# I2C_Keypad.net
KiCad netlist of a schematic drawn in Altium Designer
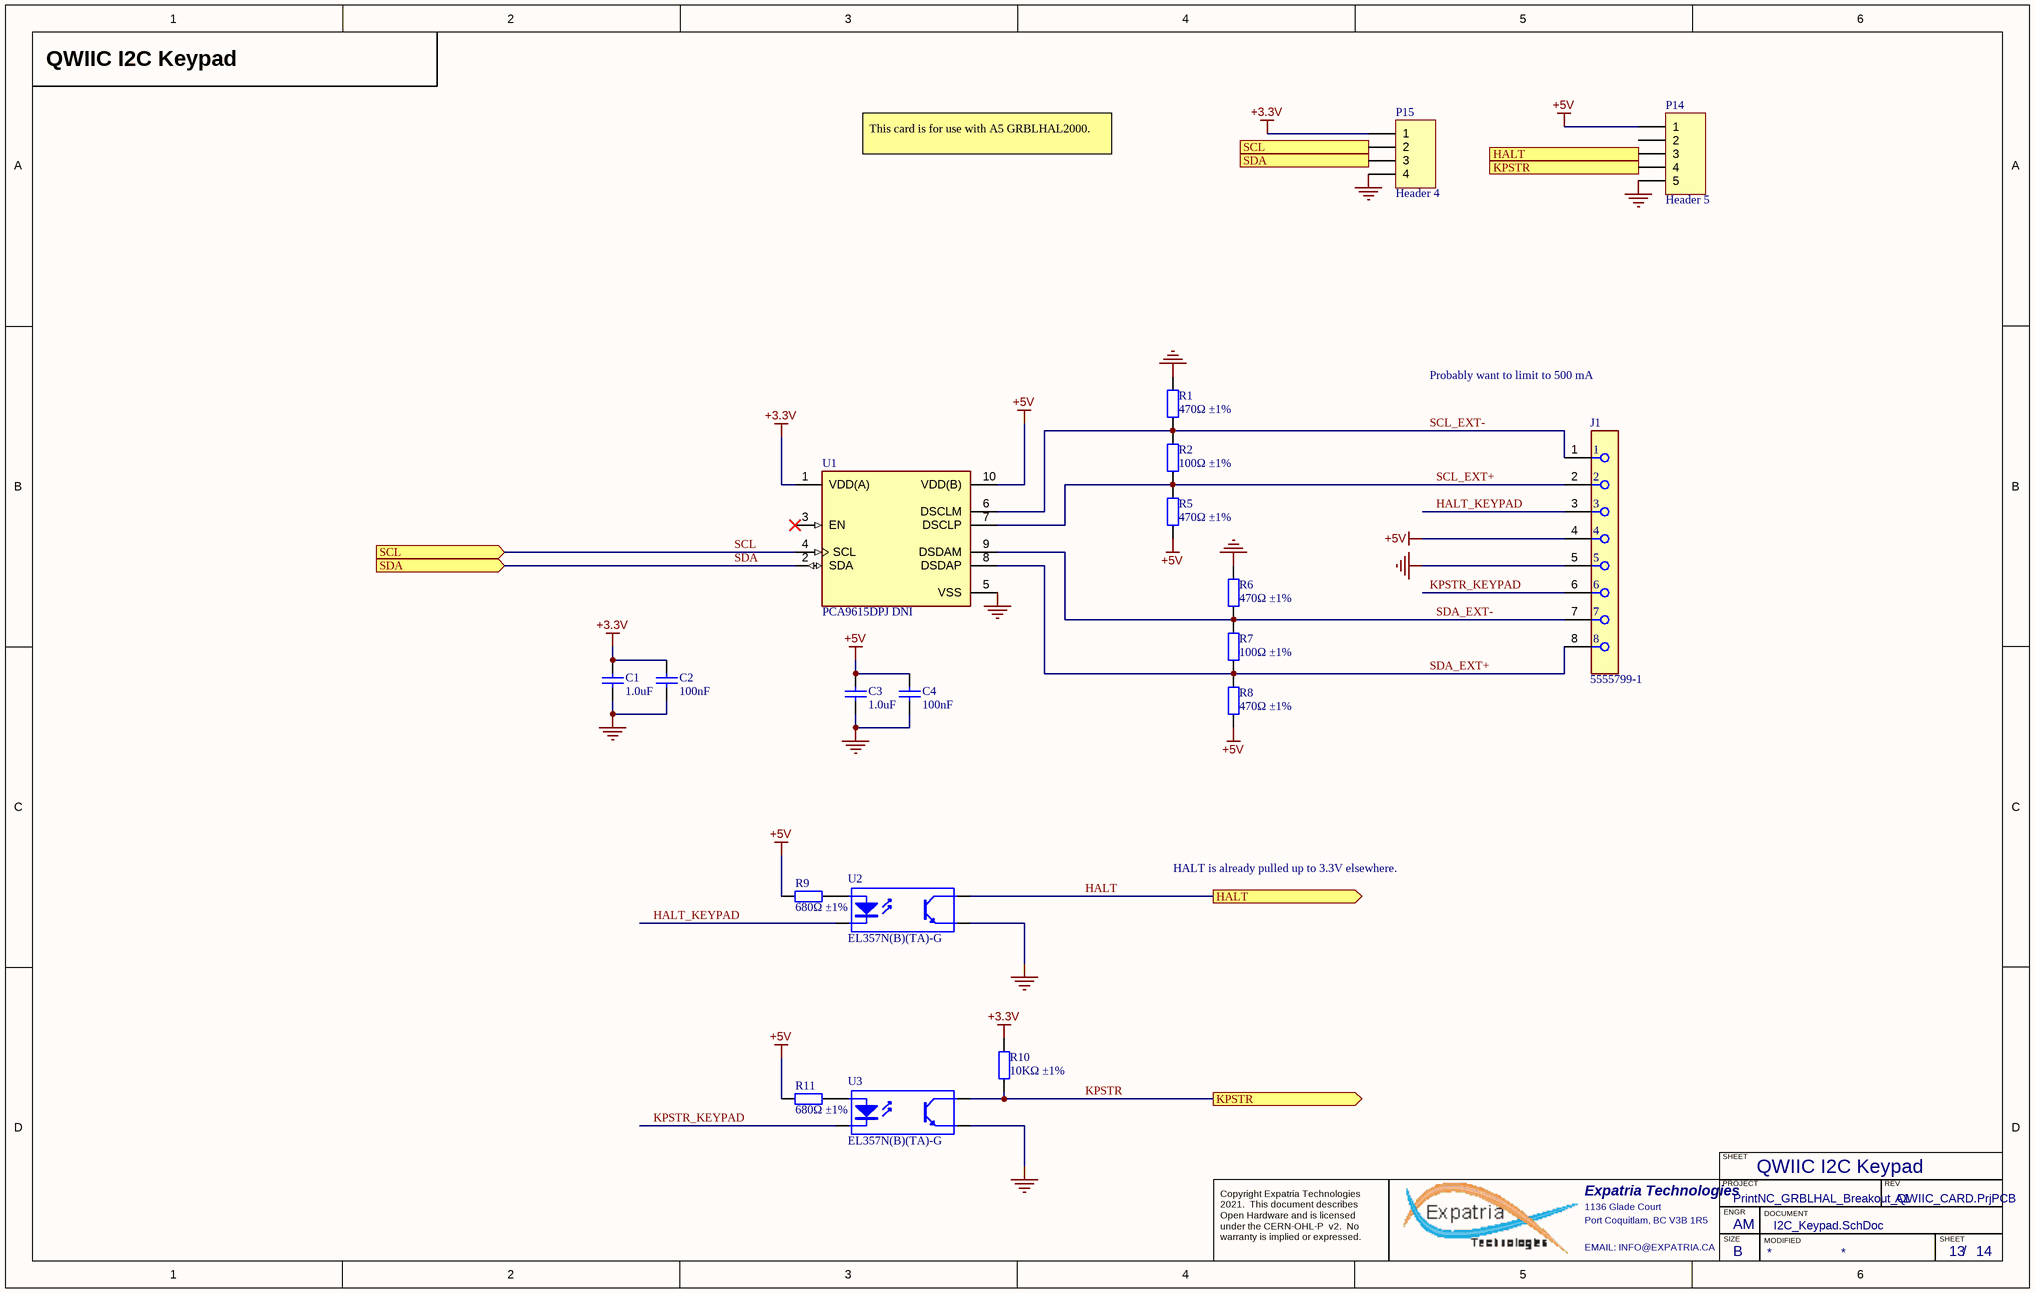
[diagram p0: I2C_Keypad.SchDoc]

(export (version "E")
  (design (tool "Eeschema 10.0.6"))
  (components
    (comp (ref "C1")
      (value "1.0uF")
      (footprint "0402_C")
      (description "Chip capacitor")
      (fields
        (field (name "MANUFACTURER") "Samsung Electro-Mechanics")
        (field (name "PARTNUMBER") "CL05A105KA5NQNC")
      )
      (libsource (lib "Cap") (part "0402 1.0uF (105) 10% 25V"))
    )
    (comp (ref "C2")
      (value "100nF")
      (footprint "0402_C")
      (description "Chip capacitors")
      (fields
        (field (name "MANUFACTURER") "Samsung Electro-Mechanics")
        (field (name "PARTNUMBER") "CL05B104KO5NNNC")
      )
      (libsource (lib "Cap") (part "0402 100nF (104) 10% 16V"))
    )
    (comp (ref "C3")
      (value "1.0uF")
      (footprint "0402_C")
      (description "Chip capacitor")
      (fields
        (field (name "MANUFACTURER") "Samsung Electro-Mechanics")
        (field (name "PARTNUMBER") "CL05A105KA5NQNC")
      )
      (libsource (lib "Cap") (part "0402 1.0uF (105) 10% 25V"))
    )
    (comp (ref "C4")
      (value "100nF")
      (footprint "0402_C")
      (description "Chip capacitors")
      (fields
        (field (name "MANUFACTURER") "Samsung Electro-Mechanics")
        (field (name "PARTNUMBER") "CL05B104KO5NNNC")
      )
      (libsource (lib "Cap") (part "0402 100nF (104) 10% 16V"))
    )
    (comp (ref "J1")
      (value "5555799-1")
      (footprint "FP-5555799-1-MFG")
      (description "CONN MOD JACK 8P8C VERT UNSHLD")
      (fields
        (field (name "MANUFACTURER") "TE Connectivity")
        (field (name "OCTOPART") "https://octopart.com/5555799-1-te+connectivity-39526335")
      )
      (libsource (lib "Altium Content Vault") (part "a32a9c29f5c2290c50060dfb8ad7212"))
    )
    (comp (ref "P14")
      (value "Header 5")
      (footprint "HDR1X5")
      (description "Header, 5-Pin")
      (fields (field (name "PUBLISHER") "Altium Limited"))
      (libsource (lib "PrintNC_GRBLHAL_Breakout") (part "Header 5"))
    )
    (comp (ref "P15")
      (value "Header 4")
      (footprint "HDR1X4")
      (description "Header, 4-Pin")
      (fields (field (name "PUBLISHER") "Altium Limited"))
      (libsource (lib "PrintNC_GRBLHAL_Breakout") (part "Header 4"))
    )
    (comp (ref "R1")
      (value "470Ω ±1%")
      (footprint "0402_R")
      (description "Chip resistor")
      (fields (field (name "MANUFACTURER") "Uniroyal Elec") (field (name "PARTNUMBER") "0402WGF4700TCE"))
      (libsource (lib "RES") (part "0402 470R (4700) 1%"))
    )
    (comp (ref "R2")
      (value "100Ω ±1%")
      (footprint "0402_R")
      (description "Chip resistor")
      (fields (field (name "MANUFACTURER") "Uniroyal Elec") (field (name "PARTNUMBER") "0402WGF1000TCE"))
      (libsource (lib "RES") (part "0402 100R (1000) 1%"))
    )
    (comp (ref "R5")
      (value "470Ω ±1%")
      (footprint "0402_R")
      (description "Chip resistor")
      (fields (field (name "MANUFACTURER") "Uniroyal Elec") (field (name "PARTNUMBER") "0402WGF4700TCE"))
      (libsource (lib "RES") (part "0402 470R (4700) 1%"))
    )
    (comp (ref "R6")
      (value "470Ω ±1%")
      (footprint "0402_R")
      (description "Chip resistor")
      (fields (field (name "MANUFACTURER") "Uniroyal Elec") (field (name "PARTNUMBER") "0402WGF4700TCE"))
      (libsource (lib "RES") (part "0402 470R (4700) 1%"))
    )
    (comp (ref "R7")
      (value "100Ω ±1%")
      (footprint "0402_R")
      (description "Chip resistor")
      (fields (field (name "MANUFACTURER") "Uniroyal Elec") (field (name "PARTNUMBER") "0402WGF1000TCE"))
      (libsource (lib "RES") (part "0402 100R (1000) 1%"))
    )
    (comp (ref "R8")
      (value "470Ω ±1%")
      (footprint "0402_R")
      (description "Chip resistor")
      (fields (field (name "MANUFACTURER") "Uniroyal Elec") (field (name "PARTNUMBER") "0402WGF4700TCE"))
      (libsource (lib "RES") (part "0402 470R (4700) 1%"))
    )
    (comp (ref "R9")
      (value "680Ω ±1%")
      (footprint "0402_R")
      (description "Chip resistor")
      (fields (field (name "MANUFACTURER") "Uniroyal Elec") (field (name "PARTNUMBER") "0402WGF6800TCE"))
      (libsource (lib "RES") (part "0402 680R (6800) 1%"))
    )
    (comp (ref "R10")
      (value "10KΩ ±1%")
      (footprint "0402_R")
      (description "Chip resistor")
      (fields (field (name "MANUFACTURER") "Uniroyal Elec") (field (name "PARTNUMBER") "0402WGF1002TCE"))
      (libsource (lib "RES") (part "0402 10K (1002) 1%"))
    )
    (comp (ref "R11")
      (value "680Ω ±1%")
      (footprint "0402_R")
      (description "Chip resistor")
      (fields (field (name "MANUFACTURER") "Uniroyal Elec") (field (name "PARTNUMBER") "0402WGF6800TCE"))
      (libsource (lib "RES") (part "0402 680R (6800) 1%"))
    )
    (comp (ref "U1")
      (value "PCA9615DPJ DNI")
      (footprint "FP-SOT552-1-IPC_C")
      (description "IC REDRIVER I2C 2CH 10TSSOP")
      (fields
        (field (name "OCTOPART") "https://octopart.com/pca9615dpj-nxp+semiconductors-34972203")
        (field (name "MANUFACTURER") "NXP")
      )
      (libsource (lib "Altium Content Vault") (part "aa97fc17a90ab6781572c98f0c4d6bd"))
    )
    (comp (ref "U2")
      (value "EL357N(B)(TA)-G")
      (footprint "SOP-4_P2.54")
      (description "贴片光耦")
      (libsource (lib "IC") (part "EL357N(B)(TA)-G_[C6649]"))
    )
    (comp (ref "U3")
      (value "EL357N(B)(TA)-G")
      (footprint "SOP-4_P2.54")
      (description "贴片光耦")
      (libsource (lib "IC") (part "EL357N(B)(TA)-G_[C6649]"))
    )
  )
  (nets
    (net (code "1") (name "+3.3V") (class "Default")
      (node (ref "C1") (pin "2") (pinfunction "2_2") (pintype "passive"))
      (node (ref "C2") (pin "2") (pinfunction "2_2") (pintype "passive"))
      (node (ref "P15") (pin "1") (pinfunction "1_1") (pintype "passive"))
      (node (ref "R10") (pin "2") (pinfunction "2_2") (pintype "passive"))
      (node (ref "U1") (pin "1") (pinfunction "VDD(A)_1") (pintype "power_in"))
    )
    (net (code "2") (name "+5V") (class "Default")
      (node (ref "C3") (pin "2") (pinfunction "2_2") (pintype "passive"))
      (node (ref "C4") (pin "2") (pinfunction "2_2") (pintype "passive"))
      (node (ref "J1") (pin "4") (pinfunction "4_4") (pintype "passive"))
      (node (ref "P14") (pin "1") (pinfunction "1_1") (pintype "passive"))
      (node (ref "R11") (pin "1") (pinfunction "1_1") (pintype "passive"))
      (node (ref "R5") (pin "1") (pinfunction "1_1") (pintype "passive"))
      (node (ref "R8") (pin "1") (pinfunction "1_1") (pintype "passive"))
      (node (ref "R9") (pin "1") (pinfunction "1_1") (pintype "passive"))
      (node (ref "U1") (pin "10") (pinfunction "VDD(B)_10") (pintype "power_in"))
    )
    (net (code "3") (name "/HALT") (class "Default")
      (node (ref "P14") (pin "3") (pinfunction "3_3") (pintype "passive"))
      (node (ref "U2") (pin "4") (pinfunction "C_4") (pintype "passive"))
    )
    (net (code "4") (name "/HALT_KEYPAD") (class "Default")
      (node (ref "J1") (pin "3") (pinfunction "3_3") (pintype "passive"))
      (node (ref "U2") (pin "2") (pinfunction "K_2") (pintype "passive"))
    )
    (net (code "5") (name "/KPSTR") (class "Default")
      (node (ref "P14") (pin "4") (pinfunction "4_4") (pintype "passive"))
      (node (ref "R10") (pin "1") (pinfunction "1_1") (pintype "passive"))
      (node (ref "U3") (pin "4") (pinfunction "C_4") (pintype "passive"))
    )
    (net (code "6") (name "/KPSTR_KEYPAD") (class "Default")
      (node (ref "J1") (pin "6") (pinfunction "6_6") (pintype "passive"))
      (node (ref "U3") (pin "2") (pinfunction "K_2") (pintype "passive"))
    )
    (net (code "7") (name "/SCL") (class "Default")
      (node (ref "P15") (pin "2") (pinfunction "2_2") (pintype "passive"))
      (node (ref "U1") (pin "4") (pinfunction "SCL_4") (pintype "input"))
    )
    (net (code "8") (name "/SCL_EXT+") (class "Default")
      (node (ref "J1") (pin "2") (pinfunction "2_2") (pintype "passive"))
      (node (ref "R2") (pin "1") (pinfunction "1_1") (pintype "passive"))
      (node (ref "R5") (pin "2") (pinfunction "2_2") (pintype "passive"))
      (node (ref "U1") (pin "7") (pinfunction "DSCLP_7") (pintype "open_collector"))
    )
    (net (code "9") (name "/SCL_EXT-") (class "Default")
      (node (ref "J1") (pin "1") (pinfunction "1_1") (pintype "passive"))
      (node (ref "R1") (pin "1") (pinfunction "1_1") (pintype "passive"))
      (node (ref "R2") (pin "2") (pinfunction "2_2") (pintype "passive"))
      (node (ref "U1") (pin "6") (pinfunction "DSCLM_6") (pintype "open_collector"))
    )
    (net (code "10") (name "/SDA") (class "Default")
      (node (ref "P15") (pin "3") (pinfunction "3_3") (pintype "passive"))
      (node (ref "U1") (pin "2") (pinfunction "SDA_2") (pintype "bidirectional"))
    )
    (net (code "11") (name "/SDA_EXT+") (class "Default")
      (node (ref "J1") (pin "8") (pinfunction "8_8") (pintype "passive"))
      (node (ref "R7") (pin "1") (pinfunction "1_1") (pintype "passive"))
      (node (ref "R8") (pin "2") (pinfunction "2_2") (pintype "passive"))
      (node (ref "U1") (pin "8") (pinfunction "DSDAP_8") (pintype "open_collector"))
    )
    (net (code "12") (name "/SDA_EXT-") (class "Default")
      (node (ref "J1") (pin "7") (pinfunction "7_7") (pintype "passive"))
      (node (ref "R6") (pin "1") (pinfunction "1_1") (pintype "passive"))
      (node (ref "R7") (pin "2") (pinfunction "2_2") (pintype "passive"))
      (node (ref "U1") (pin "9") (pinfunction "DSDAM_9") (pintype "open_collector"))
    )
    (net (code "13") (name "GND") (class "Default")
      (node (ref "C1") (pin "1") (pinfunction "1_1") (pintype "passive"))
      (node (ref "C2") (pin "1") (pinfunction "1_1") (pintype "passive"))
      (node (ref "C3") (pin "1") (pinfunction "1_1") (pintype "passive"))
      (node (ref "C4") (pin "1") (pinfunction "1_1") (pintype "passive"))
      (node (ref "J1") (pin "5") (pinfunction "5_5") (pintype "passive"))
      (node (ref "P14") (pin "5") (pinfunction "5_5") (pintype "passive"))
      (node (ref "P15") (pin "4") (pinfunction "4_4") (pintype "passive"))
      (node (ref "R1") (pin "2") (pinfunction "2_2") (pintype "passive"))
      (node (ref "R6") (pin "2") (pinfunction "2_2") (pintype "passive"))
      (node (ref "U1") (pin "5") (pinfunction "VSS_5") (pintype "power_in"))
      (node (ref "U2") (pin "3") (pinfunction "E_3") (pintype "passive"))
      (node (ref "U3") (pin "3") (pinfunction "E_3") (pintype "passive"))
    )
    (net (code "14") (name "Net-(U2-A)") (class "Default")
      (node (ref "R9") (pin "2") (pinfunction "2_2") (pintype "passive"))
      (node (ref "U2") (pin "1") (pinfunction "A_1") (pintype "passive"))
    )
    (net (code "15") (name "Net-(U3-A)") (class "Default")
      (node (ref "R11") (pin "2") (pinfunction "2_2") (pintype "passive"))
      (node (ref "U3") (pin "1") (pinfunction "A_1") (pintype "passive"))
    )
    (net (code "16") (name "unconnected-(P14-Pad2)") (class "Default")
      (node (ref "P14") (pin "2") (pinfunction "2_2") (pintype "passive"))
    )
    (net (code "17") (name "unconnected-(U1-EN-Pad3)") (class "Default")
      (node (ref "U1") (pin "3") (pinfunction "EN_3") (pintype "input+no_connect"))
    )
  )
)
